# SCH_roni555_2025-03-13.net
KiCad netlist of a schematic drawn in EasyEDA
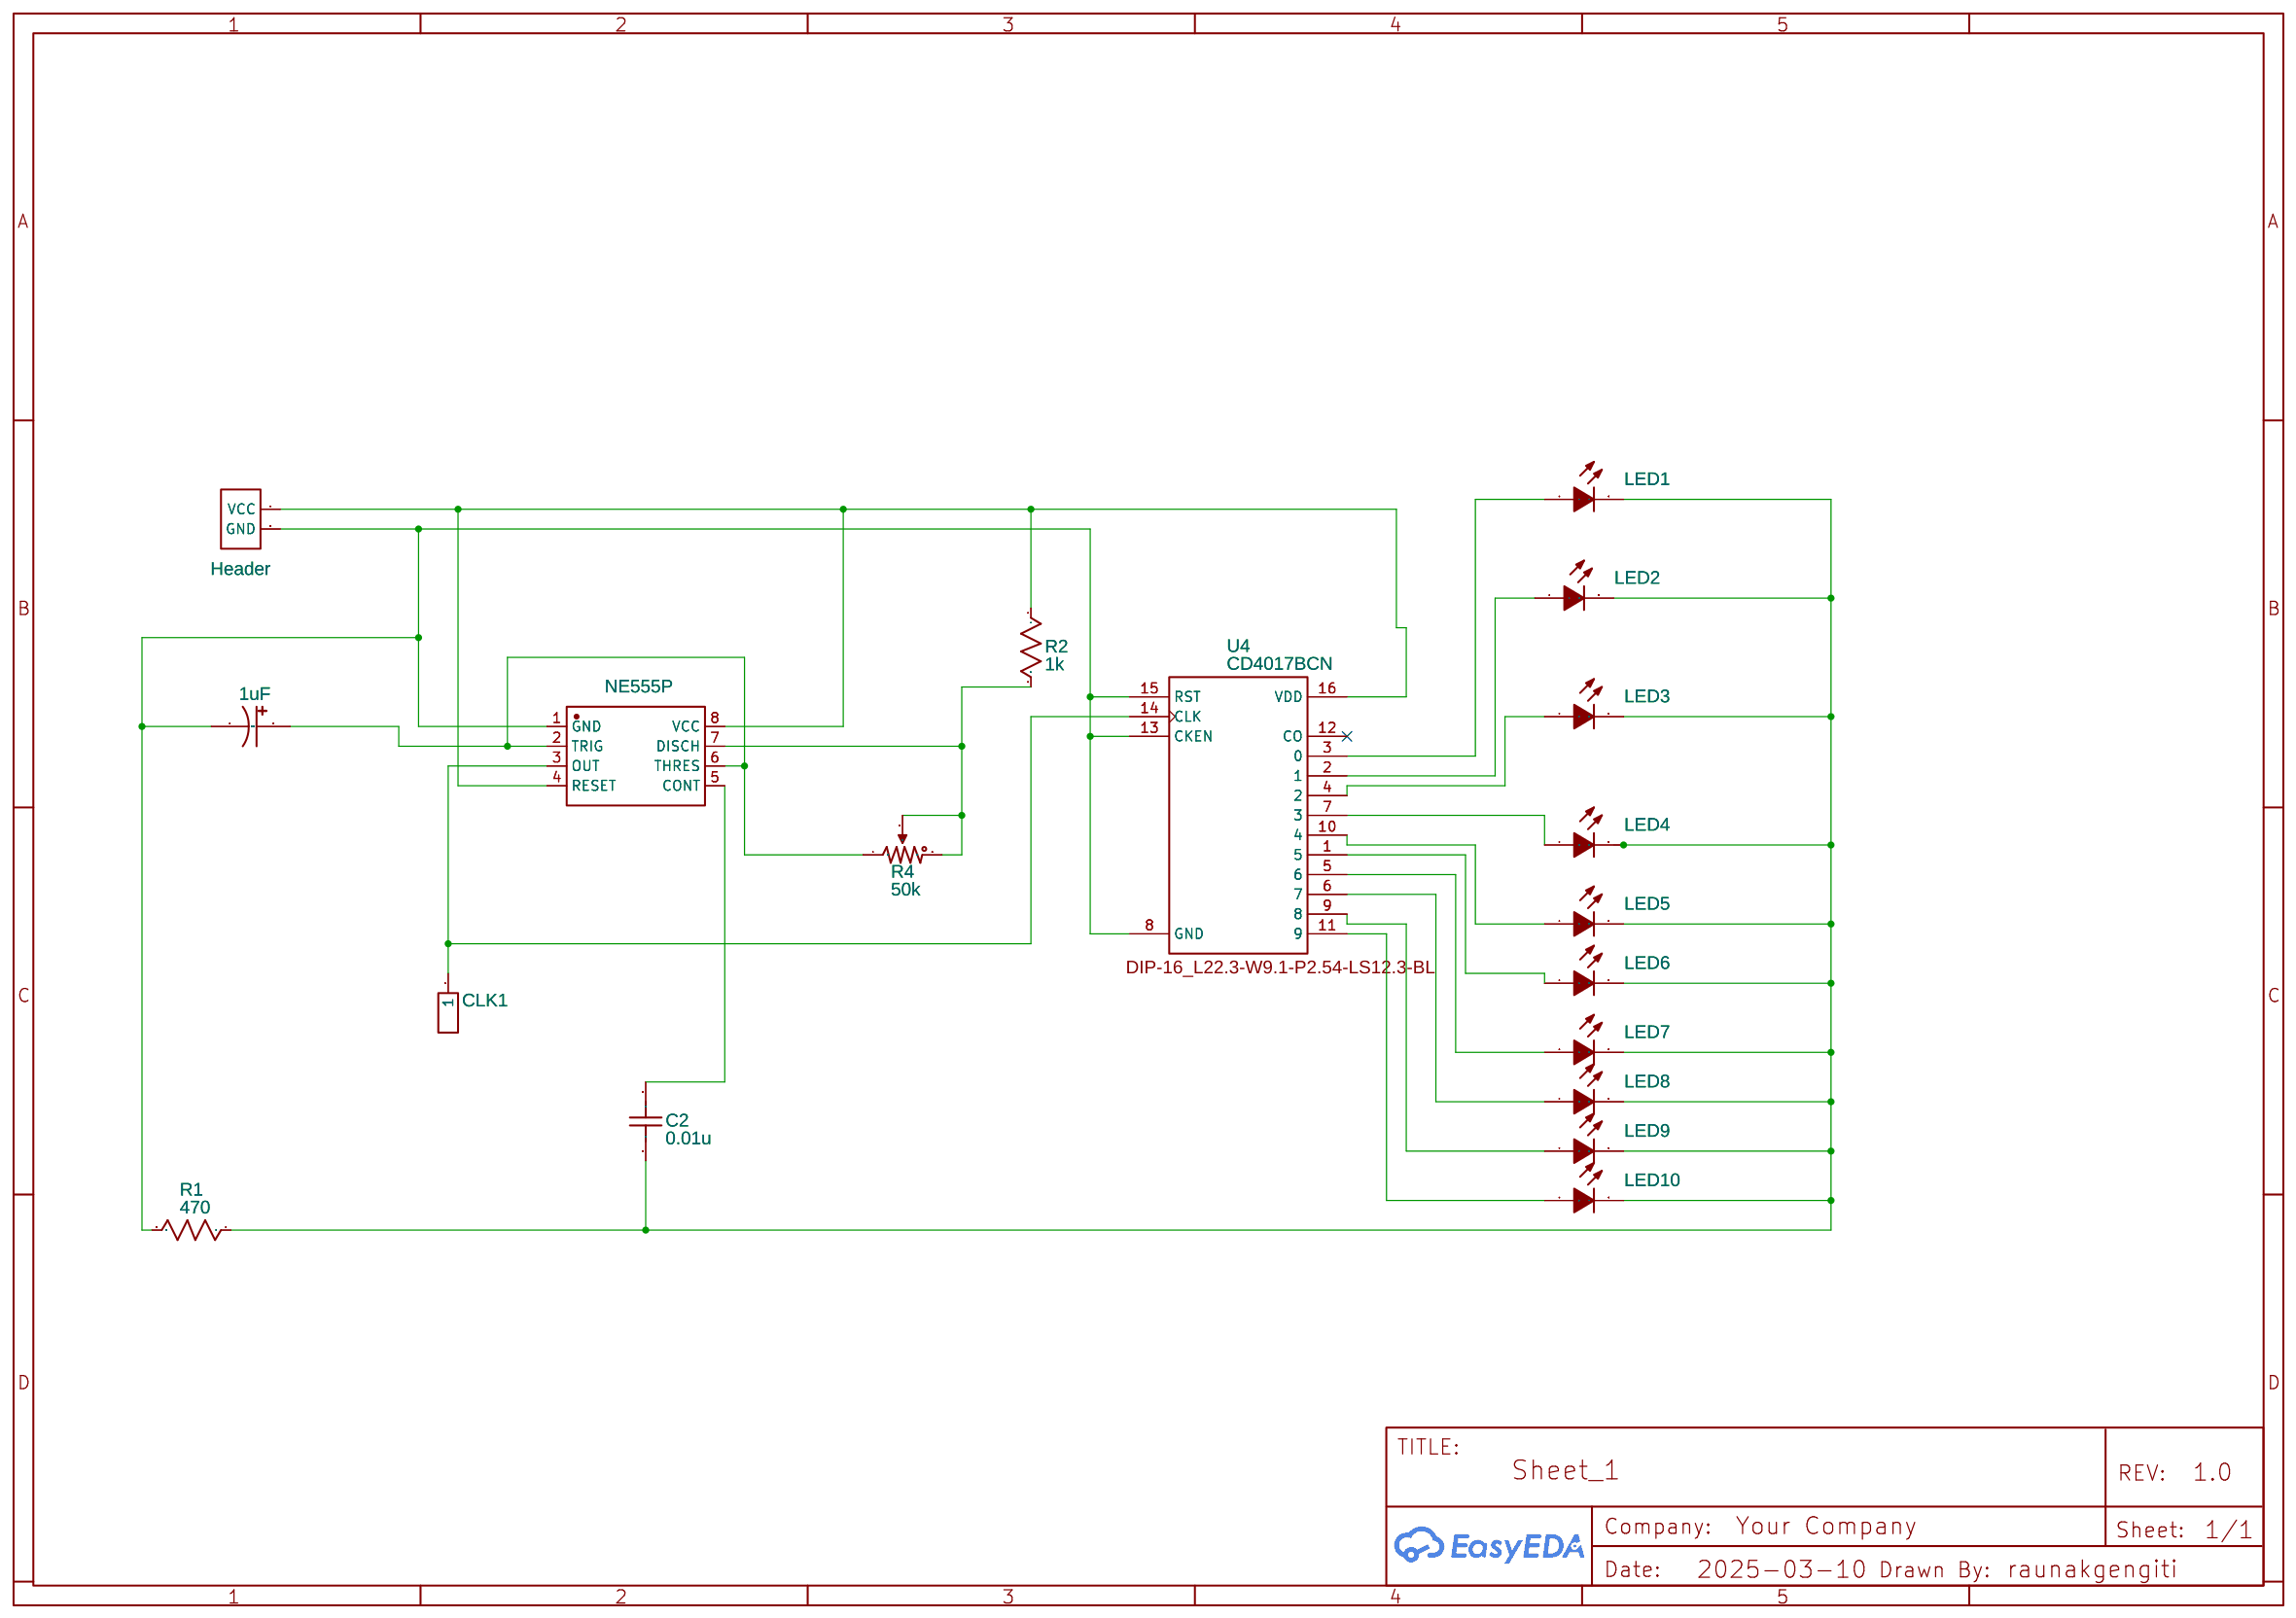
[diagram p0: schematic sheet]

(export (version "E")
  (design (tool "Eeschema 10.0.6"))
  (components
    (comp (ref "C1")
      (value "1uF")
      (fields (field (name "Manufacturer Part") "UVZ1H010MDD") (field (name "Manufacturer") "Nichicon(尼吉康)"))
      (libsource (lib "") (part "UVZ1H010MDD"))
    )
    (comp (ref "C2") (value "0.01u") (libsource (lib "") (part "C_0603_US")))
    (comp (ref "CLK1")
      (value "C81276")
      (fields
        (field (name "Manufacturer Part") "2.54-1*1P针")
        (field (name "Manufacturer") "BOOMELE(Boom Precision Elec)")
      )
      (libsource (lib "") (part "Header-Male-2.54_1x1"))
    )
    (comp (ref "H1") (value "Header") (libsource (lib "") (part "HEADER-FEMALE-2.54_1X2")))
    (comp (ref "LED1") (value "LED_5MM") (libsource (lib "") (part "LED_5MM")))
    (comp (ref "LED2") (value "LED_5MM") (libsource (lib "") (part "LED_5MM")))
    (comp (ref "LED3") (value "LED_5MM") (libsource (lib "") (part "LED_5MM")))
    (comp (ref "LED4") (value "LED_5MM") (libsource (lib "") (part "LED_5MM")))
    (comp (ref "LED5") (value "LED_5MM") (libsource (lib "") (part "LED_5MM")))
    (comp (ref "LED6") (value "LED_5MM") (libsource (lib "") (part "LED_5MM")))
    (comp (ref "LED7") (value "LED_5MM") (libsource (lib "") (part "LED_5MM")))
    (comp (ref "LED8") (value "LED_5MM") (libsource (lib "") (part "LED_5MM")))
    (comp (ref "LED9") (value "LED_5MM") (libsource (lib "") (part "LED_5MM")))
    (comp (ref "LED10") (value "LED_5MM") (libsource (lib "") (part "LED_5MM")))
    (comp (ref "R1")
      (value "470")
      (fields (field (name "Manufacturer Part") "?"))
      (libsource (lib "") (part "Resistor"))
    )
    (comp (ref "R2")
      (value "1k")
      (fields (field (name "Manufacturer Part") "?"))
      (libsource (lib "") (part "Resistor_1"))
    )
    (comp (ref "R4")
      (value "50k")
      (fields (field (name "Manufacturer Part") "?"))
      (libsource (lib "") (part "Potentiometer"))
    )
    (comp (ref "U2")
      (value "NE555P")
      (fields (field (name "Manufacturer") "TI(德州仪器)"))
      (libsource (lib "") (part "NE555P"))
    )
    (comp (ref "U4") (value "CD4017BCN") (libsource (lib "") (part "CD4017BCN")))
  )
  (nets
    (net (code "1") (name "Net-(H1-GND)") (class "Default")
      (node (ref "C1") (pin "2") (pinfunction "2_2") (pintype "unspecified"))
      (node (ref "H1") (pin "2") (pinfunction "GND_2") (pintype "unspecified"))
      (node (ref "R1") (pin "2") (pinfunction "2_2") (pintype "unspecified"))
      (node (ref "U2") (pin "1") (pinfunction "GND_1") (pintype "unspecified"))
      (node (ref "U4") (pin "13") (pinfunction "CKEN_13") (pintype "unspecified"))
      (node (ref "U4") (pin "15") (pinfunction "RST_15") (pintype "unspecified"))
      (node (ref "U4") (pin "8") (pinfunction "GND_8") (pintype "passive"))
    )
    (net (code "2") (name "Net-(H1-VCC)") (class "Default")
      (node (ref "H1") (pin "1") (pinfunction "VCC_1") (pintype "unspecified"))
      (node (ref "R2") (pin "1") (pinfunction "1_1") (pintype "unspecified"))
      (node (ref "U2") (pin "4") (pinfunction "RESET_4") (pintype "unspecified"))
      (node (ref "U2") (pin "8") (pinfunction "VCC_8") (pintype "unspecified"))
      (node (ref "U4") (pin "16") (pinfunction "VDD_16") (pintype "passive"))
    )
    (net (code "3") (name "Net-(LED1-A)") (class "Default")
      (node (ref "LED1") (pin "1") (pinfunction "A_1") (pintype "input"))
      (node (ref "U4") (pin "3") (pinfunction "0_3") (pintype "output"))
    )
    (net (code "4") (name "Net-(LED1-K)") (class "Default")
      (node (ref "C2") (pin "1") (pinfunction "1_1") (pintype "unspecified"))
      (node (ref "LED1") (pin "2") (pinfunction "K_2") (pintype "input"))
      (node (ref "LED10") (pin "2") (pinfunction "K_2") (pintype "input"))
      (node (ref "LED2") (pin "2") (pinfunction "K_2") (pintype "input"))
      (node (ref "LED3") (pin "2") (pinfunction "K_2") (pintype "input"))
      (node (ref "LED4") (pin "2") (pinfunction "K_2") (pintype "input"))
      (node (ref "LED5") (pin "2") (pinfunction "K_2") (pintype "input"))
      (node (ref "LED6") (pin "2") (pinfunction "K_2") (pintype "input"))
      (node (ref "LED7") (pin "2") (pinfunction "K_2") (pintype "input"))
      (node (ref "LED8") (pin "2") (pinfunction "K_2") (pintype "input"))
      (node (ref "LED9") (pin "2") (pinfunction "K_2") (pintype "input"))
      (node (ref "R1") (pin "1") (pinfunction "1_1") (pintype "unspecified"))
    )
    (net (code "5") (name "Net-(LED2-A)") (class "Default")
      (node (ref "LED2") (pin "1") (pinfunction "A_1") (pintype "input"))
      (node (ref "U4") (pin "2") (pinfunction "1_2") (pintype "output"))
    )
    (net (code "6") (name "Net-(LED3-A)") (class "Default")
      (node (ref "LED3") (pin "1") (pinfunction "A_1") (pintype "input"))
      (node (ref "U4") (pin "4") (pinfunction "2_4") (pintype "output"))
    )
    (net (code "7") (name "Net-(LED4-A)") (class "Default")
      (node (ref "LED4") (pin "1") (pinfunction "A_1") (pintype "input"))
      (node (ref "U4") (pin "7") (pinfunction "3_7") (pintype "output"))
    )
    (net (code "8") (name "Net-(LED5-A)") (class "Default")
      (node (ref "LED5") (pin "1") (pinfunction "A_1") (pintype "input"))
      (node (ref "U4") (pin "10") (pinfunction "4_10") (pintype "output"))
    )
    (net (code "9") (name "Net-(LED6-A)") (class "Default")
      (node (ref "LED6") (pin "1") (pinfunction "A_1") (pintype "input"))
      (node (ref "U4") (pin "1") (pinfunction "5_1") (pintype "output"))
    )
    (net (code "10") (name "Net-(LED7-A)") (class "Default")
      (node (ref "LED7") (pin "1") (pinfunction "A_1") (pintype "input"))
      (node (ref "U4") (pin "5") (pinfunction "6_5") (pintype "output"))
    )
    (net (code "11") (name "Net-(LED8-A)") (class "Default")
      (node (ref "LED8") (pin "1") (pinfunction "A_1") (pintype "input"))
      (node (ref "U4") (pin "6") (pinfunction "7_6") (pintype "output"))
    )
    (net (code "12") (name "Net-(LED9-A)") (class "Default")
      (node (ref "LED9") (pin "1") (pinfunction "A_1") (pintype "input"))
      (node (ref "U4") (pin "9") (pinfunction "8_9") (pintype "output"))
    )
    (net (code "13") (name "Net-(LED10-A)") (class "Default")
      (node (ref "LED10") (pin "1") (pinfunction "A_1") (pintype "input"))
      (node (ref "U4") (pin "11") (pinfunction "9_11") (pintype "output"))
    )
    (net (code "14") (name "Net-(R4-2)") (class "Default")
      (node (ref "R2") (pin "2") (pinfunction "2_2") (pintype "unspecified"))
      (node (ref "R4") (pin "2") (pinfunction "3_2") (pintype "unspecified"))
      (node (ref "R4") (pin "3") (pinfunction "2_3") (pintype "unspecified"))
      (node (ref "U2") (pin "7") (pinfunction "DISCH_7") (pintype "unspecified"))
    )
    (net (code "15") (name "Net-(U2-CONT)") (class "Default")
      (node (ref "C2") (pin "2") (pinfunction "2_2") (pintype "unspecified"))
      (node (ref "U2") (pin "5") (pinfunction "CONT_5") (pintype "unspecified"))
    )
    (net (code "16") (name "Net-(U2-OUT)") (class "Default")
      (node (ref "CLK1") (pin "1") (pinfunction "1_1") (pintype "unspecified"))
      (node (ref "U2") (pin "3") (pinfunction "OUT_3") (pintype "unspecified"))
      (node (ref "U4") (pin "14") (pinfunction "CLK_14") (pintype "unspecified"))
    )
    (net (code "17") (name "Net-(U2-THRES)") (class "Default")
      (node (ref "C1") (pin "1") (pinfunction "1_1") (pintype "unspecified"))
      (node (ref "R4") (pin "1") (pinfunction "1_1") (pintype "unspecified"))
      (node (ref "U2") (pin "2") (pinfunction "TRIG_2") (pintype "unspecified"))
      (node (ref "U2") (pin "6") (pinfunction "THRES_6") (pintype "unspecified"))
    )
    (net (code "18") (name "unconnected-(U4-CO-Pad12)") (class "Default")
      (node (ref "U4") (pin "12") (pinfunction "CO_12") (pintype "output+no_connect"))
    )
  )
)
